# 05_PWMdriver.net
KiCad netlist of a schematic drawn in Altium Designer
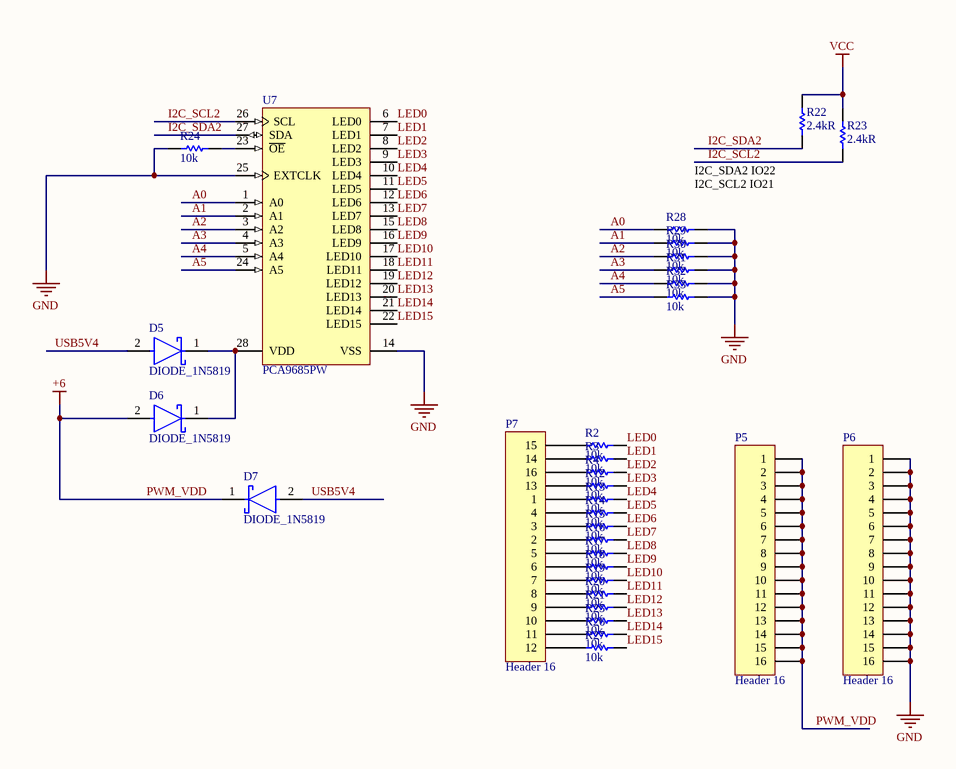
[diagram p0: 05_PWMdriver.SchDoc]

(export (version "E")
  (design (tool "Eeschema 10.0.6"))
  (components
    (comp (ref "D5")
      (value "DIODE_1N5819")
      (footprint "FP-SOD123-MFG")
      (description "DIODE SCHOTTKY 40V 1A SOD123")
      (fields
        (field (name "OCTOPART") "https://octopart.com/1n5819hw-7-f-diodes+inc.-323197")
        (field (name "MANUFACTURER") "Diodes Inc")
      )
      (libsource (lib "Altium Content Vault") (part "1d6ec82d83fb6aee721767c19dac4b9"))
    )
    (comp (ref "D6")
      (value "DIODE_1N5819")
      (footprint "FP-SOD123-MFG")
      (description "DIODE SCHOTTKY 40V 1A SOD123")
      (fields
        (field (name "OCTOPART") "https://octopart.com/1n5819hw-7-f-diodes+inc.-323197")
        (field (name "MANUFACTURER") "Diodes Inc")
      )
      (libsource (lib "Altium Content Vault") (part "1d6ec82d83fb6aee721767c19dac4b9"))
    )
    (comp (ref "D7")
      (value "DIODE_1N5819")
      (footprint "FP-SOD123-MFG")
      (description "DIODE SCHOTTKY 40V 1A SOD123")
      (fields
        (field (name "OCTOPART") "https://octopart.com/1n5819hw-7-f-diodes+inc.-323197")
        (field (name "MANUFACTURER") "Diodes Inc")
      )
      (libsource (lib "Altium Content Vault") (part "1d6ec82d83fb6aee721767c19dac4b9"))
    )
    (comp (ref "P5")
      (value "Header 16")
      (footprint "HDR1X16")
      (description "Header, 16-Pin")
      (fields (field (name "PUBLISHER") "Altium Limited"))
      (libsource (lib "Miscellaneous Connectors") (part "Header 16"))
    )
    (comp (ref "P6")
      (value "Header 16")
      (footprint "HDR1X16")
      (description "Header, 16-Pin")
      (fields (field (name "PUBLISHER") "Altium Limited"))
      (libsource (lib "Miscellaneous Connectors") (part "Header 16"))
    )
    (comp (ref "P7")
      (value "Header 16")
      (footprint "HDR1X16")
      (description "Header, 16-Pin")
      (fields (field (name "PUBLISHER") "Altium Limited"))
      (libsource (lib "") (part "Header 16_1"))
    )
    (comp (ref "R2")
      (value "10k")
      (footprint "RESC1609X55X30LL15T15")
      (description "Chip Resistor, 10 KOhm, +/- 1%, 0.1 W, -55 to 155 degC, 0603 (1608 Metric), RoHS, Tape and Reel")
      (fields (field (name "TOLERANCE") "1%") (field (name "MANUFACTURER") "Panasonic"))
      (libsource (lib "Altium Content Vault") (part "RES-2"))
    )
    (comp (ref "R3")
      (value "10k")
      (footprint "RESC1609X55X30LL15T15")
      (description "Chip Resistor, 10 KOhm, +/- 1%, 0.1 W, -55 to 155 degC, 0603 (1608 Metric), RoHS, Tape and Reel")
      (fields (field (name "TOLERANCE") "1%") (field (name "MANUFACTURER") "Panasonic"))
      (libsource (lib "Altium Content Vault") (part "RES-2"))
    )
    (comp (ref "R4")
      (value "10k")
      (footprint "RESC1609X55X30LL15T15")
      (description "Chip Resistor, 10 KOhm, +/- 1%, 0.1 W, -55 to 155 degC, 0603 (1608 Metric), RoHS, Tape and Reel")
      (fields (field (name "TOLERANCE") "1%") (field (name "MANUFACTURER") "Panasonic"))
      (libsource (lib "Altium Content Vault") (part "RES-2"))
    )
    (comp (ref "R12")
      (value "10k")
      (footprint "RESC1609X55X30LL15T15")
      (description "Chip Resistor, 10 KOhm, +/- 1%, 0.1 W, -55 to 155 degC, 0603 (1608 Metric), RoHS, Tape and Reel")
      (fields (field (name "TOLERANCE") "1%") (field (name "MANUFACTURER") "Panasonic"))
      (libsource (lib "Altium Content Vault") (part "RES-2"))
    )
    (comp (ref "R13")
      (value "10k")
      (footprint "RESC1609X55X30LL15T15")
      (description "Chip Resistor, 10 KOhm, +/- 1%, 0.1 W, -55 to 155 degC, 0603 (1608 Metric), RoHS, Tape and Reel")
      (fields (field (name "TOLERANCE") "1%") (field (name "MANUFACTURER") "Panasonic"))
      (libsource (lib "Altium Content Vault") (part "RES-2"))
    )
    (comp (ref "R14")
      (value "10k")
      (footprint "RESC1609X55X30LL15T15")
      (description "Chip Resistor, 10 KOhm, +/- 1%, 0.1 W, -55 to 155 degC, 0603 (1608 Metric), RoHS, Tape and Reel")
      (fields (field (name "TOLERANCE") "1%") (field (name "MANUFACTURER") "Panasonic"))
      (libsource (lib "Altium Content Vault") (part "RES-2"))
    )
    (comp (ref "R15")
      (value "10k")
      (footprint "RESC1609X55X30LL15T15")
      (description "Chip Resistor, 10 KOhm, +/- 1%, 0.1 W, -55 to 155 degC, 0603 (1608 Metric), RoHS, Tape and Reel")
      (fields (field (name "TOLERANCE") "1%") (field (name "MANUFACTURER") "Panasonic"))
      (libsource (lib "Altium Content Vault") (part "RES-2"))
    )
    (comp (ref "R16")
      (value "10k")
      (footprint "RESC1609X55X30LL15T15")
      (description "Chip Resistor, 10 KOhm, +/- 1%, 0.1 W, -55 to 155 degC, 0603 (1608 Metric), RoHS, Tape and Reel")
      (fields (field (name "TOLERANCE") "1%") (field (name "MANUFACTURER") "Panasonic"))
      (libsource (lib "Altium Content Vault") (part "RES-2"))
    )
    (comp (ref "R17")
      (value "10k")
      (footprint "RESC1609X55X30LL15T15")
      (description "Chip Resistor, 10 KOhm, +/- 1%, 0.1 W, -55 to 155 degC, 0603 (1608 Metric), RoHS, Tape and Reel")
      (fields (field (name "TOLERANCE") "1%") (field (name "MANUFACTURER") "Panasonic"))
      (libsource (lib "Altium Content Vault") (part "RES-2"))
    )
    (comp (ref "R18")
      (value "10k")
      (footprint "RESC1609X55X30LL15T15")
      (description "Chip Resistor, 10 KOhm, +/- 1%, 0.1 W, -55 to 155 degC, 0603 (1608 Metric), RoHS, Tape and Reel")
      (fields (field (name "TOLERANCE") "1%") (field (name "MANUFACTURER") "Panasonic"))
      (libsource (lib "Altium Content Vault") (part "RES-2"))
    )
    (comp (ref "R19")
      (value "10k")
      (footprint "RESC1609X55X30LL15T15")
      (description "Chip Resistor, 10 KOhm, +/- 1%, 0.1 W, -55 to 155 degC, 0603 (1608 Metric), RoHS, Tape and Reel")
      (fields (field (name "TOLERANCE") "1%") (field (name "MANUFACTURER") "Panasonic"))
      (libsource (lib "Altium Content Vault") (part "RES-2"))
    )
    (comp (ref "R20")
      (value "10k")
      (footprint "RESC1609X55X30LL15T15")
      (description "Chip Resistor, 10 KOhm, +/- 1%, 0.1 W, -55 to 155 degC, 0603 (1608 Metric), RoHS, Tape and Reel")
      (fields (field (name "TOLERANCE") "1%") (field (name "MANUFACTURER") "Panasonic"))
      (libsource (lib "Altium Content Vault") (part "RES-2"))
    )
    (comp (ref "R21")
      (value "10k")
      (footprint "RESC1609X55X30LL15T15")
      (description "Chip Resistor, 10 KOhm, +/- 1%, 0.1 W, -55 to 155 degC, 0603 (1608 Metric), RoHS, Tape and Reel")
      (fields (field (name "TOLERANCE") "1%") (field (name "MANUFACTURER") "Panasonic"))
      (libsource (lib "Altium Content Vault") (part "RES-2"))
    )
    (comp (ref "R22")
      (value "2.4kR")
      (footprint "RESC1608X50X30ML20T20")
      (fields
        (field (name "PART NUMBER") "RR0816P-242-D")
        (field (name "MANUFACTURER") "Susumu")
        (field (name "Comment") "R0603_2.4K")
      )
      (libsource (lib "Altium Content Vault") (part "RES"))
    )
    (comp (ref "R23")
      (value "2.4kR")
      (footprint "RESC1608X50X30ML20T20")
      (fields
        (field (name "PART NUMBER") "RR0816P-242-D")
        (field (name "MANUFACTURER") "Susumu")
        (field (name "Comment") "R0603_2.4K")
      )
      (libsource (lib "Altium Content Vault") (part "RES"))
    )
    (comp (ref "R24")
      (value "10k")
      (footprint "RESC1609X55X30LL15T15")
      (description "Chip Resistor, 10 KOhm, +/- 1%, 0.1 W, -55 to 155 degC, 0603 (1608 Metric), RoHS, Tape and Reel")
      (fields (field (name "TOLERANCE") "1%") (field (name "MANUFACTURER") "Panasonic"))
      (libsource (lib "Altium Content Vault") (part "RES-2"))
    )
    (comp (ref "R25")
      (value "10k")
      (footprint "RESC1609X55X30LL15T15")
      (description "Chip Resistor, 10 KOhm, +/- 1%, 0.1 W, -55 to 155 degC, 0603 (1608 Metric), RoHS, Tape and Reel")
      (fields (field (name "TOLERANCE") "1%") (field (name "MANUFACTURER") "Panasonic"))
      (libsource (lib "Altium Content Vault") (part "RES-2"))
    )
    (comp (ref "R26")
      (value "10k")
      (footprint "RESC1609X55X30LL15T15")
      (description "Chip Resistor, 10 KOhm, +/- 1%, 0.1 W, -55 to 155 degC, 0603 (1608 Metric), RoHS, Tape and Reel")
      (fields (field (name "TOLERANCE") "1%") (field (name "MANUFACTURER") "Panasonic"))
      (libsource (lib "Altium Content Vault") (part "RES-2"))
    )
    (comp (ref "R27")
      (value "10k")
      (footprint "RESC1609X55X30LL15T15")
      (description "Chip Resistor, 10 KOhm, +/- 1%, 0.1 W, -55 to 155 degC, 0603 (1608 Metric), RoHS, Tape and Reel")
      (fields (field (name "TOLERANCE") "1%") (field (name "MANUFACTURER") "Panasonic"))
      (libsource (lib "Altium Content Vault") (part "RES-2"))
    )
    (comp (ref "R28")
      (value "10k")
      (footprint "RESC1609X55X30LL15T15")
      (description "Chip Resistor, 10 KOhm, +/- 1%, 0.1 W, -55 to 155 degC, 0603 (1608 Metric), RoHS, Tape and Reel")
      (fields (field (name "TOLERANCE") "1%") (field (name "MANUFACTURER") "Panasonic"))
      (libsource (lib "Altium Content Vault") (part "RES-2"))
    )
    (comp (ref "R29")
      (value "10k")
      (footprint "RESC1609X55X30LL15T15")
      (description "Chip Resistor, 10 KOhm, +/- 1%, 0.1 W, -55 to 155 degC, 0603 (1608 Metric), RoHS, Tape and Reel")
      (fields (field (name "TOLERANCE") "1%") (field (name "MANUFACTURER") "Panasonic"))
      (libsource (lib "Altium Content Vault") (part "RES-2"))
    )
    (comp (ref "R30")
      (value "10k")
      (footprint "RESC1609X55X30LL15T15")
      (description "Chip Resistor, 10 KOhm, +/- 1%, 0.1 W, -55 to 155 degC, 0603 (1608 Metric), RoHS, Tape and Reel")
      (fields (field (name "TOLERANCE") "1%") (field (name "MANUFACTURER") "Panasonic"))
      (libsource (lib "Altium Content Vault") (part "RES-2"))
    )
    (comp (ref "R31")
      (value "10k")
      (footprint "RESC1609X55X30LL15T15")
      (description "Chip Resistor, 10 KOhm, +/- 1%, 0.1 W, -55 to 155 degC, 0603 (1608 Metric), RoHS, Tape and Reel")
      (fields (field (name "TOLERANCE") "1%") (field (name "MANUFACTURER") "Panasonic"))
      (libsource (lib "Altium Content Vault") (part "RES-2"))
    )
    (comp (ref "R32")
      (value "10k")
      (footprint "RESC1609X55X30LL15T15")
      (description "Chip Resistor, 10 KOhm, +/- 1%, 0.1 W, -55 to 155 degC, 0603 (1608 Metric), RoHS, Tape and Reel")
      (fields (field (name "TOLERANCE") "1%") (field (name "MANUFACTURER") "Panasonic"))
      (libsource (lib "Altium Content Vault") (part "RES-2"))
    )
    (comp (ref "R33")
      (value "10k")
      (footprint "RESC1609X55X30LL15T15")
      (description "Chip Resistor, 10 KOhm, +/- 1%, 0.1 W, -55 to 155 degC, 0603 (1608 Metric), RoHS, Tape and Reel")
      (fields (field (name "TOLERANCE") "1%") (field (name "MANUFACTURER") "Panasonic"))
      (libsource (lib "Altium Content Vault") (part "RES-2"))
    )
    (comp (ref "U7")
      (value "PCA9685PW")
      (footprint "SOT361-1_V")
      (fields (field (name "PARTNUMBER") "PCA9685"))
      (libsource (lib "Altium Content Vault") (part "NXP-PCA9685-SOT361-1"))
    )
  )
  (nets
    (net (code "1") (name "+6") (class "Default")
      (node (ref "D6") (pin "2") (pinfunction "A_2") (pintype "passive"))
      (node (ref "D7") (pin "1") (pinfunction "C_1") (pintype "passive"))
      (node (ref "P5") (pin "1") (pinfunction "1_1") (pintype "passive"))
      (node (ref "P5") (pin "10") (pinfunction "10_10") (pintype "passive"))
      (node (ref "P5") (pin "11") (pinfunction "11_11") (pintype "passive"))
      (node (ref "P5") (pin "12") (pinfunction "12_12") (pintype "passive"))
      (node (ref "P5") (pin "13") (pinfunction "13_13") (pintype "passive"))
      (node (ref "P5") (pin "14") (pinfunction "14_14") (pintype "passive"))
      (node (ref "P5") (pin "15") (pinfunction "15_15") (pintype "passive"))
      (node (ref "P5") (pin "16") (pinfunction "16_16") (pintype "passive"))
      (node (ref "P5") (pin "2") (pinfunction "2_2") (pintype "passive"))
      (node (ref "P5") (pin "3") (pinfunction "3_3") (pintype "passive"))
      (node (ref "P5") (pin "4") (pinfunction "4_4") (pintype "passive"))
      (node (ref "P5") (pin "5") (pinfunction "5_5") (pintype "passive"))
      (node (ref "P5") (pin "6") (pinfunction "6_6") (pintype "passive"))
      (node (ref "P5") (pin "7") (pinfunction "7_7") (pintype "passive"))
      (node (ref "P5") (pin "8") (pinfunction "8_8") (pintype "passive"))
      (node (ref "P5") (pin "9") (pinfunction "9_9") (pintype "passive"))
    )
    (net (code "2") (name "/A0") (class "Default")
      (node (ref "R28") (pin "2") (pinfunction "2_2") (pintype "passive"))
      (node (ref "U7") (pin "1") (pinfunction "A0_1") (pintype "input"))
    )
    (net (code "3") (name "/A1") (class "Default")
      (node (ref "R29") (pin "2") (pinfunction "2_2") (pintype "passive"))
      (node (ref "U7") (pin "2") (pinfunction "A1_2") (pintype "input"))
    )
    (net (code "4") (name "/A2") (class "Default")
      (node (ref "R30") (pin "2") (pinfunction "2_2") (pintype "passive"))
      (node (ref "U7") (pin "3") (pinfunction "A2_3") (pintype "input"))
    )
    (net (code "5") (name "/A3") (class "Default")
      (node (ref "R31") (pin "2") (pinfunction "2_2") (pintype "passive"))
      (node (ref "U7") (pin "4") (pinfunction "A3_4") (pintype "input"))
    )
    (net (code "6") (name "/A4") (class "Default")
      (node (ref "R32") (pin "2") (pinfunction "2_2") (pintype "passive"))
      (node (ref "U7") (pin "5") (pinfunction "A4_5") (pintype "input"))
    )
    (net (code "7") (name "/A5") (class "Default")
      (node (ref "R33") (pin "2") (pinfunction "2_2") (pintype "passive"))
      (node (ref "U7") (pin "24") (pinfunction "A5_24") (pintype "input"))
    )
    (net (code "8") (name "/I2C_SCL2") (class "Default")
      (node (ref "R23") (pin "1") (pinfunction "1_1") (pintype "passive"))
      (node (ref "U7") (pin "26") (pinfunction "SCL_26") (pintype "input"))
    )
    (net (code "9") (name "/I2C_SDA2") (class "Default")
      (node (ref "R22") (pin "1") (pinfunction "1_1") (pintype "passive"))
      (node (ref "U7") (pin "27") (pinfunction "SDA_27") (pintype "bidirectional"))
    )
    (net (code "10") (name "/LED0") (class "Default")
      (node (ref "R2") (pin "1") (pinfunction "1_1") (pintype "passive"))
      (node (ref "U7") (pin "6") (pinfunction "LED0_6") (pintype "tri_state"))
    )
    (net (code "11") (name "/LED1") (class "Default")
      (node (ref "R3") (pin "1") (pinfunction "1_1") (pintype "passive"))
      (node (ref "U7") (pin "7") (pinfunction "LED1_7") (pintype "tri_state"))
    )
    (net (code "12") (name "/LED2") (class "Default")
      (node (ref "R4") (pin "1") (pinfunction "1_1") (pintype "passive"))
      (node (ref "U7") (pin "8") (pinfunction "LED2_8") (pintype "tri_state"))
    )
    (net (code "13") (name "/LED3") (class "Default")
      (node (ref "R12") (pin "1") (pinfunction "1_1") (pintype "passive"))
      (node (ref "U7") (pin "9") (pinfunction "LED3_9") (pintype "tri_state"))
    )
    (net (code "14") (name "/LED4") (class "Default")
      (node (ref "R13") (pin "1") (pinfunction "1_1") (pintype "passive"))
      (node (ref "U7") (pin "10") (pinfunction "LED4_10") (pintype "tri_state"))
    )
    (net (code "15") (name "/LED5") (class "Default")
      (node (ref "R14") (pin "1") (pinfunction "1_1") (pintype "passive"))
      (node (ref "U7") (pin "11") (pinfunction "LED5_11") (pintype "tri_state"))
    )
    (net (code "16") (name "/LED6") (class "Default")
      (node (ref "R15") (pin "1") (pinfunction "1_1") (pintype "passive"))
      (node (ref "U7") (pin "12") (pinfunction "LED6_12") (pintype "tri_state"))
    )
    (net (code "17") (name "/LED7") (class "Default")
      (node (ref "R16") (pin "1") (pinfunction "1_1") (pintype "passive"))
      (node (ref "U7") (pin "13") (pinfunction "LED7_13") (pintype "tri_state"))
    )
    (net (code "18") (name "/LED8") (class "Default")
      (node (ref "R17") (pin "1") (pinfunction "1_1") (pintype "passive"))
      (node (ref "U7") (pin "15") (pinfunction "LED8_15") (pintype "tri_state"))
    )
    (net (code "19") (name "/LED9") (class "Default")
      (node (ref "R18") (pin "1") (pinfunction "1_1") (pintype "passive"))
      (node (ref "U7") (pin "16") (pinfunction "LED9_16") (pintype "tri_state"))
    )
    (net (code "20") (name "/LED10") (class "Default")
      (node (ref "R19") (pin "1") (pinfunction "1_1") (pintype "passive"))
      (node (ref "U7") (pin "17") (pinfunction "LED10_17") (pintype "tri_state"))
    )
    (net (code "21") (name "/LED11") (class "Default")
      (node (ref "R20") (pin "1") (pinfunction "1_1") (pintype "passive"))
      (node (ref "U7") (pin "18") (pinfunction "LED11_18") (pintype "tri_state"))
    )
    (net (code "22") (name "/LED12") (class "Default")
      (node (ref "R21") (pin "1") (pinfunction "1_1") (pintype "passive"))
      (node (ref "U7") (pin "19") (pinfunction "LED12_19") (pintype "tri_state"))
    )
    (net (code "23") (name "/LED13") (class "Default")
      (node (ref "R25") (pin "1") (pinfunction "1_1") (pintype "passive"))
      (node (ref "U7") (pin "20") (pinfunction "LED13_20") (pintype "tri_state"))
    )
    (net (code "24") (name "/LED14") (class "Default")
      (node (ref "R26") (pin "1") (pinfunction "1_1") (pintype "passive"))
      (node (ref "U7") (pin "21") (pinfunction "LED14_21") (pintype "tri_state"))
    )
    (net (code "25") (name "/LED15") (class "Default")
      (node (ref "R27") (pin "1") (pinfunction "1_1") (pintype "passive"))
      (node (ref "U7") (pin "22") (pinfunction "LED15_22") (pintype "tri_state"))
    )
    (net (code "26") (name "/USB5V4") (class "Default")
      (node (ref "D5") (pin "2") (pinfunction "A_2") (pintype "passive"))
      (node (ref "D7") (pin "2") (pinfunction "A_2") (pintype "passive"))
    )
    (net (code "27") (name "GND") (class "Default")
      (node (ref "P6") (pin "1") (pinfunction "1_1") (pintype "passive"))
      (node (ref "P6") (pin "10") (pinfunction "10_10") (pintype "passive"))
      (node (ref "P6") (pin "11") (pinfunction "11_11") (pintype "passive"))
      (node (ref "P6") (pin "12") (pinfunction "12_12") (pintype "passive"))
      (node (ref "P6") (pin "13") (pinfunction "13_13") (pintype "passive"))
      (node (ref "P6") (pin "14") (pinfunction "14_14") (pintype "passive"))
      (node (ref "P6") (pin "15") (pinfunction "15_15") (pintype "passive"))
      (node (ref "P6") (pin "16") (pinfunction "16_16") (pintype "passive"))
      (node (ref "P6") (pin "2") (pinfunction "2_2") (pintype "passive"))
      (node (ref "P6") (pin "3") (pinfunction "3_3") (pintype "passive"))
      (node (ref "P6") (pin "4") (pinfunction "4_4") (pintype "passive"))
      (node (ref "P6") (pin "5") (pinfunction "5_5") (pintype "passive"))
      (node (ref "P6") (pin "6") (pinfunction "6_6") (pintype "passive"))
      (node (ref "P6") (pin "7") (pinfunction "7_7") (pintype "passive"))
      (node (ref "P6") (pin "8") (pinfunction "8_8") (pintype "passive"))
      (node (ref "P6") (pin "9") (pinfunction "9_9") (pintype "passive"))
      (node (ref "R24") (pin "2") (pinfunction "2_2") (pintype "passive"))
      (node (ref "R28") (pin "1") (pinfunction "1_1") (pintype "passive"))
      (node (ref "R29") (pin "1") (pinfunction "1_1") (pintype "passive"))
      (node (ref "R30") (pin "1") (pinfunction "1_1") (pintype "passive"))
      (node (ref "R31") (pin "1") (pinfunction "1_1") (pintype "passive"))
      (node (ref "R32") (pin "1") (pinfunction "1_1") (pintype "passive"))
      (node (ref "R33") (pin "1") (pinfunction "1_1") (pintype "passive"))
      (node (ref "U7") (pin "14") (pinfunction "VSS_14") (pintype "power_in"))
      (node (ref "U7") (pin "25") (pinfunction "EXTCLK_25") (pintype "input"))
    )
    (net (code "28") (name "Net-(D5-C)") (class "Default")
      (node (ref "D5") (pin "1") (pinfunction "C_1") (pintype "passive"))
      (node (ref "D6") (pin "1") (pinfunction "C_1") (pintype "passive"))
      (node (ref "U7") (pin "28") (pinfunction "VDD_28") (pintype "power_in"))
    )
    (net (code "29") (name "Net-(P7-Pad1)") (class "Default")
      (node (ref "P7") (pin "1") (pinfunction "1_1") (pintype "passive"))
      (node (ref "R13") (pin "2") (pinfunction "2_2") (pintype "passive"))
    )
    (net (code "30") (name "Net-(P7-Pad2)") (class "Default")
      (node (ref "P7") (pin "2") (pinfunction "2_2") (pintype "passive"))
      (node (ref "R16") (pin "2") (pinfunction "2_2") (pintype "passive"))
    )
    (net (code "31") (name "Net-(P7-Pad3)") (class "Default")
      (node (ref "P7") (pin "3") (pinfunction "3_3") (pintype "passive"))
      (node (ref "R15") (pin "2") (pinfunction "2_2") (pintype "passive"))
    )
    (net (code "32") (name "Net-(P7-Pad4)") (class "Default")
      (node (ref "P7") (pin "4") (pinfunction "4_4") (pintype "passive"))
      (node (ref "R14") (pin "2") (pinfunction "2_2") (pintype "passive"))
    )
    (net (code "33") (name "Net-(P7-Pad5)") (class "Default")
      (node (ref "P7") (pin "5") (pinfunction "5_5") (pintype "passive"))
      (node (ref "R17") (pin "2") (pinfunction "2_2") (pintype "passive"))
    )
    (net (code "34") (name "Net-(P7-Pad6)") (class "Default")
      (node (ref "P7") (pin "6") (pinfunction "6_6") (pintype "passive"))
      (node (ref "R18") (pin "2") (pinfunction "2_2") (pintype "passive"))
    )
    (net (code "35") (name "Net-(P7-Pad7)") (class "Default")
      (node (ref "P7") (pin "7") (pinfunction "7_7") (pintype "passive"))
      (node (ref "R19") (pin "2") (pinfunction "2_2") (pintype "passive"))
    )
    (net (code "36") (name "Net-(P7-Pad8)") (class "Default")
      (node (ref "P7") (pin "8") (pinfunction "8_8") (pintype "passive"))
      (node (ref "R20") (pin "2") (pinfunction "2_2") (pintype "passive"))
    )
    (net (code "37") (name "Net-(P7-Pad9)") (class "Default")
      (node (ref "P7") (pin "9") (pinfunction "9_9") (pintype "passive"))
      (node (ref "R21") (pin "2") (pinfunction "2_2") (pintype "passive"))
    )
    (net (code "38") (name "Net-(P7-Pad10)") (class "Default")
      (node (ref "P7") (pin "10") (pinfunction "10_10") (pintype "passive"))
      (node (ref "R25") (pin "2") (pinfunction "2_2") (pintype "passive"))
    )
    (net (code "39") (name "Net-(P7-Pad11)") (class "Default")
      (node (ref "P7") (pin "11") (pinfunction "11_11") (pintype "passive"))
      (node (ref "R26") (pin "2") (pinfunction "2_2") (pintype "passive"))
    )
    (net (code "40") (name "Net-(P7-Pad12)") (class "Default")
      (node (ref "P7") (pin "12") (pinfunction "12_12") (pintype "passive"))
      (node (ref "R27") (pin "2") (pinfunction "2_2") (pintype "passive"))
    )
    (net (code "41") (name "Net-(P7-Pad13)") (class "Default")
      (node (ref "P7") (pin "13") (pinfunction "13_13") (pintype "passive"))
      (node (ref "R12") (pin "2") (pinfunction "2_2") (pintype "passive"))
    )
    (net (code "42") (name "Net-(P7-Pad14)") (class "Default")
      (node (ref "P7") (pin "14") (pinfunction "14_14") (pintype "passive"))
      (node (ref "R3") (pin "2") (pinfunction "2_2") (pintype "passive"))
    )
    (net (code "43") (name "Net-(P7-Pad15)") (class "Default")
      (node (ref "P7") (pin "15") (pinfunction "15_15") (pintype "passive"))
      (node (ref "R2") (pin "2") (pinfunction "2_2") (pintype "passive"))
    )
    (net (code "44") (name "Net-(P7-Pad16)") (class "Default")
      (node (ref "P7") (pin "16") (pinfunction "16_16") (pintype "passive"))
      (node (ref "R4") (pin "2") (pinfunction "2_2") (pintype "passive"))
    )
    (net (code "45") (name "Net-(U7-~{OE})") (class "Default")
      (node (ref "R24") (pin "1") (pinfunction "1_1") (pintype "passive"))
      (node (ref "U7") (pin "23") (pinfunction "~{OE}_23") (pintype "input"))
    )
    (net (code "46") (name "VCC") (class "Default")
      (node (ref "R22") (pin "2") (pinfunction "2_2") (pintype "passive"))
      (node (ref "R23") (pin "2") (pinfunction "2_2") (pintype "passive"))
    )
  )
)
